# power_indicator_right.net
KiCad netlist of a schematic drawn in EAGLE
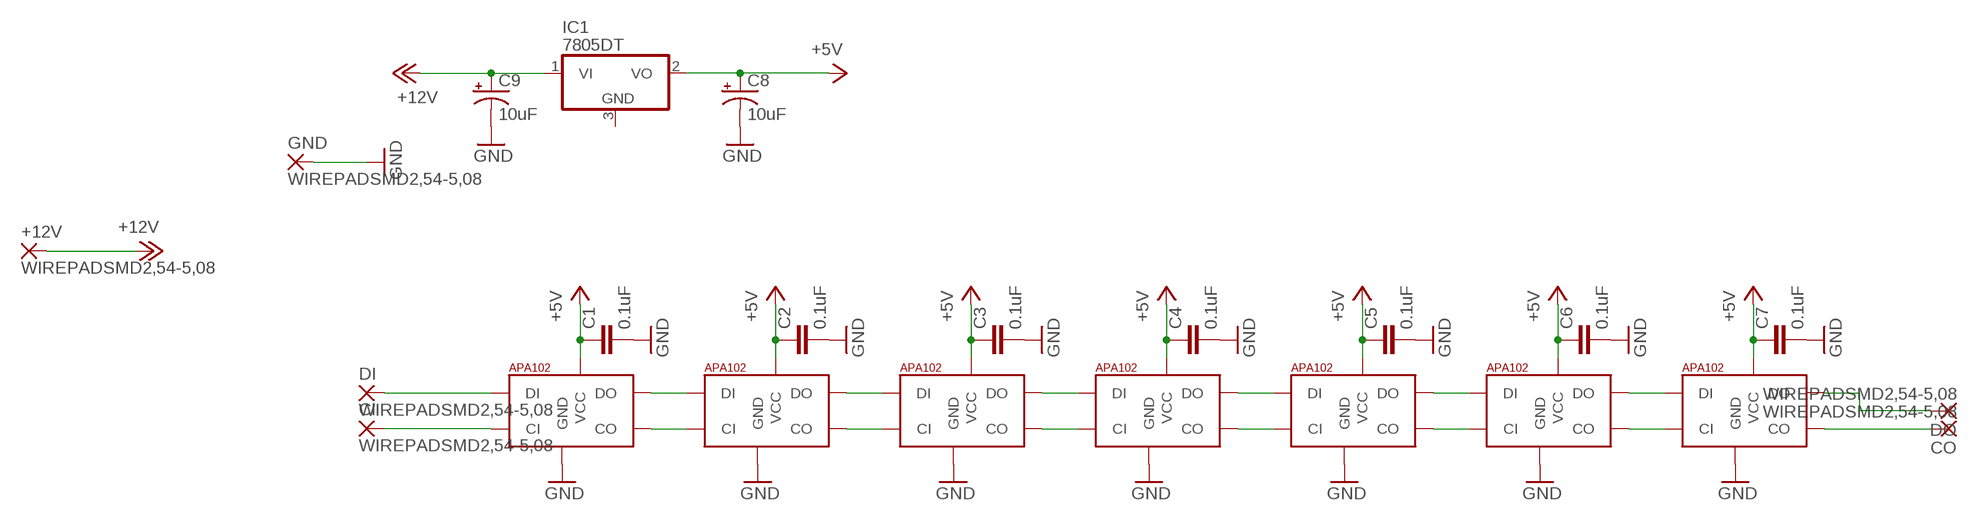
[diagram p0: schematic, sheet 1]

(export (version "E")
  (design (tool "Eeschema 10.0.6"))
  (components
    (comp (ref "+12V")
      (value "WIREPADSMD2,54-5,08")
      (footprint "eagle-import:SMD2,54-5,08")
      (libsource (lib "eagle-import") (part "WIREPADSMD2,54-5,08"))
    )
    (comp (ref "C1")
      (value "0.1uF")
      (footprint "eagle-import:0603-CAP")
      (libsource (lib "eagle-import") (part "0.1UF-100V-10%(0603)"))
    )
    (comp (ref "C2")
      (value "0.1uF")
      (footprint "eagle-import:0603-CAP")
      (libsource (lib "eagle-import") (part "0.1UF-100V-10%(0603)"))
    )
    (comp (ref "C3")
      (value "0.1uF")
      (footprint "eagle-import:0603-CAP")
      (libsource (lib "eagle-import") (part "0.1UF-100V-10%(0603)"))
    )
    (comp (ref "C4")
      (value "0.1uF")
      (footprint "eagle-import:0603-CAP")
      (libsource (lib "eagle-import") (part "0.1UF-100V-10%(0603)"))
    )
    (comp (ref "C5")
      (value "0.1uF")
      (footprint "eagle-import:0603-CAP")
      (libsource (lib "eagle-import") (part "0.1UF-100V-10%(0603)"))
    )
    (comp (ref "C6")
      (value "0.1uF")
      (footprint "eagle-import:0603-CAP")
      (libsource (lib "eagle-import") (part "0.1UF-100V-10%(0603)"))
    )
    (comp (ref "C7")
      (value "0.1uF")
      (footprint "eagle-import:0603-CAP")
      (libsource (lib "eagle-import") (part "0.1UF-100V-10%(0603)"))
    )
    (comp (ref "C8")
      (value "10uF")
      (footprint "eagle-import:EIA3216")
      (libsource (lib "eagle-import") (part "10UF-TANT"))
    )
    (comp (ref "C9")
      (value "10uF")
      (footprint "eagle-import:EIA3216")
      (libsource (lib "eagle-import") (part "10UF-TANT"))
    )
    (comp (ref "CI")
      (value "WIREPADSMD2,54-5,08")
      (footprint "eagle-import:SMD2,54-5,08")
      (libsource (lib "eagle-import") (part "WIREPADSMD2,54-5,08"))
    )
    (comp (ref "CO")
      (value "WIREPADSMD2,54-5,08")
      (footprint "eagle-import:SMD2,54-5,08")
      (libsource (lib "eagle-import") (part "WIREPADSMD2,54-5,08"))
    )
    (comp (ref "DI")
      (value "WIREPADSMD2,54-5,08")
      (footprint "eagle-import:SMD2,54-5,08")
      (libsource (lib "eagle-import") (part "WIREPADSMD2,54-5,08"))
    )
    (comp (ref "DO")
      (value "WIREPADSMD2,54-5,08")
      (footprint "eagle-import:SMD2,54-5,08")
      (libsource (lib "eagle-import") (part "WIREPADSMD2,54-5,08"))
    )
    (comp (ref "GND")
      (value "WIREPADSMD2,54-5,08")
      (footprint "eagle-import:SMD2,54-5,08")
      (libsource (lib "eagle-import") (part "WIREPADSMD2,54-5,08"))
    )
    (comp (ref "IC1")
      (value "7805DT")
      (footprint "eagle-import:TO252")
      (libsource (lib "eagle-import") (part "78DT05"))
    )
    (comp (ref "U$1")
      (value "APA1025050")
      (footprint "eagle-import:APA102_5050")
      (libsource (lib "eagle-import") (part "APA1025050"))
    )
    (comp (ref "U$2")
      (value "APA1025050")
      (footprint "eagle-import:APA102_5050")
      (libsource (lib "eagle-import") (part "APA1025050"))
    )
    (comp (ref "U$3")
      (value "APA1025050")
      (footprint "eagle-import:APA102_5050")
      (libsource (lib "eagle-import") (part "APA1025050"))
    )
    (comp (ref "U$4")
      (value "APA1025050")
      (footprint "eagle-import:APA102_5050")
      (libsource (lib "eagle-import") (part "APA1025050"))
    )
    (comp (ref "U$5")
      (value "APA1025050")
      (footprint "eagle-import:APA102_5050")
      (libsource (lib "eagle-import") (part "APA1025050"))
    )
    (comp (ref "U$6")
      (value "APA1025050")
      (footprint "eagle-import:APA102_5050")
      (libsource (lib "eagle-import") (part "APA1025050"))
    )
    (comp (ref "U$7")
      (value "APA1025050")
      (footprint "eagle-import:APA102_5050")
      (libsource (lib "eagle-import") (part "APA1025050"))
    )
  )
  (nets
    (net (code "1") (name "+5V") (class "Default")
      (node (ref "C1") (pin "1") (pinfunction "1_1") (pintype "passive"))
      (node (ref "C2") (pin "1") (pinfunction "1_1") (pintype "passive"))
      (node (ref "C3") (pin "1") (pinfunction "1_1") (pintype "passive"))
      (node (ref "C4") (pin "1") (pinfunction "1_1") (pintype "passive"))
      (node (ref "C5") (pin "1") (pinfunction "1_1") (pintype "passive"))
      (node (ref "C6") (pin "1") (pinfunction "1_1") (pintype "passive"))
      (node (ref "C7") (pin "1") (pinfunction "1_1") (pintype "passive"))
      (node (ref "C8") (pin "A") (pinfunction "+_A") (pintype "passive"))
      (node (ref "IC1") (pin "2") (pinfunction "VO_2") (pintype "passive"))
      (node (ref "U$1") (pin "1") (pinfunction "VCC_1") (pintype "bidirectional"))
      (node (ref "U$2") (pin "1") (pinfunction "VCC_1") (pintype "bidirectional"))
      (node (ref "U$3") (pin "1") (pinfunction "VCC_1") (pintype "bidirectional"))
      (node (ref "U$4") (pin "1") (pinfunction "VCC_1") (pintype "bidirectional"))
      (node (ref "U$5") (pin "1") (pinfunction "VCC_1") (pintype "bidirectional"))
      (node (ref "U$6") (pin "1") (pinfunction "VCC_1") (pintype "bidirectional"))
      (node (ref "U$7") (pin "1") (pinfunction "VCC_1") (pintype "bidirectional"))
    )
    (net (code "2") (name "+12V") (class "Default")
      (node (ref "+12V") (pin "1") (pinfunction "P_1") (pintype "passive"))
      (node (ref "C9") (pin "A") (pinfunction "+_A") (pintype "passive"))
      (node (ref "IC1") (pin "1") (pinfunction "VI_1") (pintype "input"))
    )
    (net (code "3") (name "GND") (class "Default")
      (node (ref "C1") (pin "2") (pinfunction "2_2") (pintype "passive"))
      (node (ref "C2") (pin "2") (pinfunction "2_2") (pintype "passive"))
      (node (ref "C3") (pin "2") (pinfunction "2_2") (pintype "passive"))
      (node (ref "C4") (pin "2") (pinfunction "2_2") (pintype "passive"))
      (node (ref "C5") (pin "2") (pinfunction "2_2") (pintype "passive"))
      (node (ref "C6") (pin "2") (pinfunction "2_2") (pintype "passive"))
      (node (ref "C7") (pin "2") (pinfunction "2_2") (pintype "passive"))
      (node (ref "C8") (pin "C") (pinfunction "-_C") (pintype "passive"))
      (node (ref "C9") (pin "C") (pinfunction "-_C") (pintype "passive"))
      (node (ref "GND") (pin "1") (pinfunction "P_1") (pintype "passive"))
      (node (ref "U$1") (pin "6") (pinfunction "GND_6") (pintype "bidirectional"))
      (node (ref "U$2") (pin "6") (pinfunction "GND_6") (pintype "bidirectional"))
      (node (ref "U$3") (pin "6") (pinfunction "GND_6") (pintype "bidirectional"))
      (node (ref "U$4") (pin "6") (pinfunction "GND_6") (pintype "bidirectional"))
      (node (ref "U$5") (pin "6") (pinfunction "GND_6") (pintype "bidirectional"))
      (node (ref "U$6") (pin "6") (pinfunction "GND_6") (pintype "bidirectional"))
      (node (ref "U$7") (pin "6") (pinfunction "GND_6") (pintype "bidirectional"))
    )
    (net (code "4") (name "Net-(CI-P)") (class "Default")
      (node (ref "CI") (pin "1") (pinfunction "P_1") (pintype "passive"))
      (node (ref "U$1") (pin "5") (pinfunction "CI_5") (pintype "bidirectional"))
    )
    (net (code "5") (name "Net-(CO-P)") (class "Default")
      (node (ref "CO") (pin "1") (pinfunction "P_1") (pintype "passive"))
      (node (ref "U$7") (pin "2") (pinfunction "CO_2") (pintype "bidirectional"))
    )
    (net (code "6") (name "Net-(DI-P)") (class "Default")
      (node (ref "DI") (pin "1") (pinfunction "P_1") (pintype "passive"))
      (node (ref "U$1") (pin "4") (pinfunction "DI_4") (pintype "bidirectional"))
    )
    (net (code "7") (name "Net-(DO-P)") (class "Default")
      (node (ref "DO") (pin "1") (pinfunction "P_1") (pintype "passive"))
      (node (ref "U$7") (pin "3") (pinfunction "DO_3") (pintype "bidirectional"))
    )
    (net (code "8") (name "Net-(U$1-CO)") (class "Default")
      (node (ref "U$1") (pin "2") (pinfunction "CO_2") (pintype "bidirectional"))
      (node (ref "U$2") (pin "5") (pinfunction "CI_5") (pintype "bidirectional"))
    )
    (net (code "9") (name "Net-(U$1-DO)") (class "Default")
      (node (ref "U$1") (pin "3") (pinfunction "DO_3") (pintype "bidirectional"))
      (node (ref "U$2") (pin "4") (pinfunction "DI_4") (pintype "bidirectional"))
    )
    (net (code "10") (name "Net-(U$2-CO)") (class "Default")
      (node (ref "U$2") (pin "2") (pinfunction "CO_2") (pintype "bidirectional"))
      (node (ref "U$3") (pin "5") (pinfunction "CI_5") (pintype "bidirectional"))
    )
    (net (code "11") (name "Net-(U$2-DO)") (class "Default")
      (node (ref "U$2") (pin "3") (pinfunction "DO_3") (pintype "bidirectional"))
      (node (ref "U$3") (pin "4") (pinfunction "DI_4") (pintype "bidirectional"))
    )
    (net (code "12") (name "Net-(U$3-CO)") (class "Default")
      (node (ref "U$3") (pin "2") (pinfunction "CO_2") (pintype "bidirectional"))
      (node (ref "U$4") (pin "5") (pinfunction "CI_5") (pintype "bidirectional"))
    )
    (net (code "13") (name "Net-(U$3-DO)") (class "Default")
      (node (ref "U$3") (pin "3") (pinfunction "DO_3") (pintype "bidirectional"))
      (node (ref "U$4") (pin "4") (pinfunction "DI_4") (pintype "bidirectional"))
    )
    (net (code "14") (name "Net-(U$4-CO)") (class "Default")
      (node (ref "U$4") (pin "2") (pinfunction "CO_2") (pintype "bidirectional"))
      (node (ref "U$5") (pin "5") (pinfunction "CI_5") (pintype "bidirectional"))
    )
    (net (code "15") (name "Net-(U$4-DO)") (class "Default")
      (node (ref "U$4") (pin "3") (pinfunction "DO_3") (pintype "bidirectional"))
      (node (ref "U$5") (pin "4") (pinfunction "DI_4") (pintype "bidirectional"))
    )
    (net (code "16") (name "Net-(U$5-CO)") (class "Default")
      (node (ref "U$5") (pin "2") (pinfunction "CO_2") (pintype "bidirectional"))
      (node (ref "U$6") (pin "5") (pinfunction "CI_5") (pintype "bidirectional"))
    )
    (net (code "17") (name "Net-(U$5-DO)") (class "Default")
      (node (ref "U$5") (pin "3") (pinfunction "DO_3") (pintype "bidirectional"))
      (node (ref "U$6") (pin "4") (pinfunction "DI_4") (pintype "bidirectional"))
    )
    (net (code "18") (name "Net-(U$6-CO)") (class "Default")
      (node (ref "U$6") (pin "2") (pinfunction "CO_2") (pintype "bidirectional"))
      (node (ref "U$7") (pin "5") (pinfunction "CI_5") (pintype "bidirectional"))
    )
    (net (code "19") (name "Net-(U$6-DO)") (class "Default")
      (node (ref "U$6") (pin "3") (pinfunction "DO_3") (pintype "bidirectional"))
      (node (ref "U$7") (pin "4") (pinfunction "DI_4") (pintype "bidirectional"))
    )
    (net (code "20") (name "unconnected-(IC1-GND-Pad3)") (class "Default")
      (node (ref "IC1") (pin "3") (pinfunction "GND_3") (pintype "passive"))
    )
  )
)
